# axiom_beta_plugin_module_TE0714_SATA_v0_.net
KiCad netlist of a schematic drawn in EAGLE
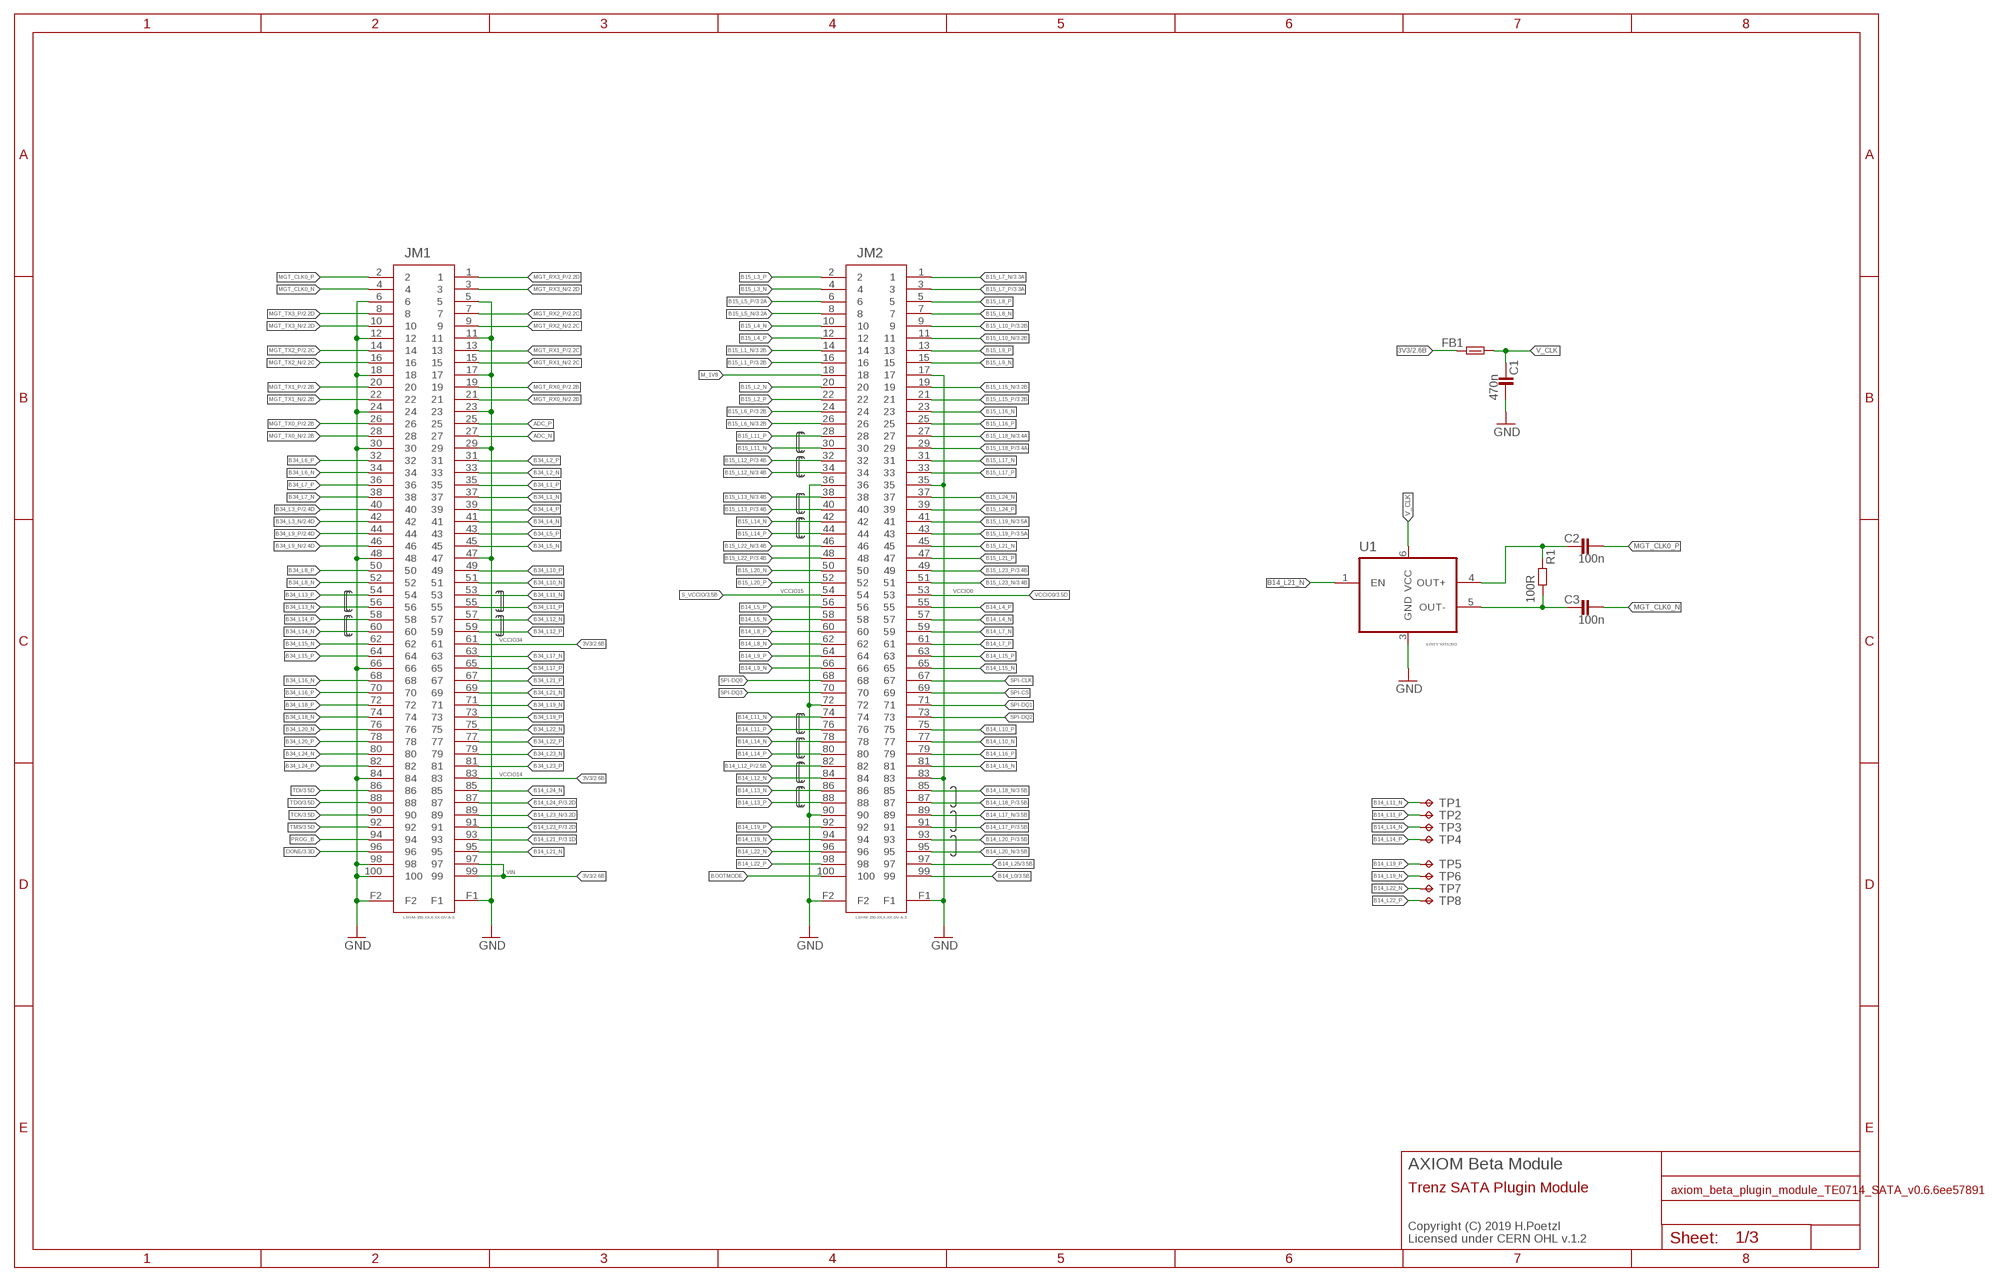
[diagram p0: schematic, sheet 1]
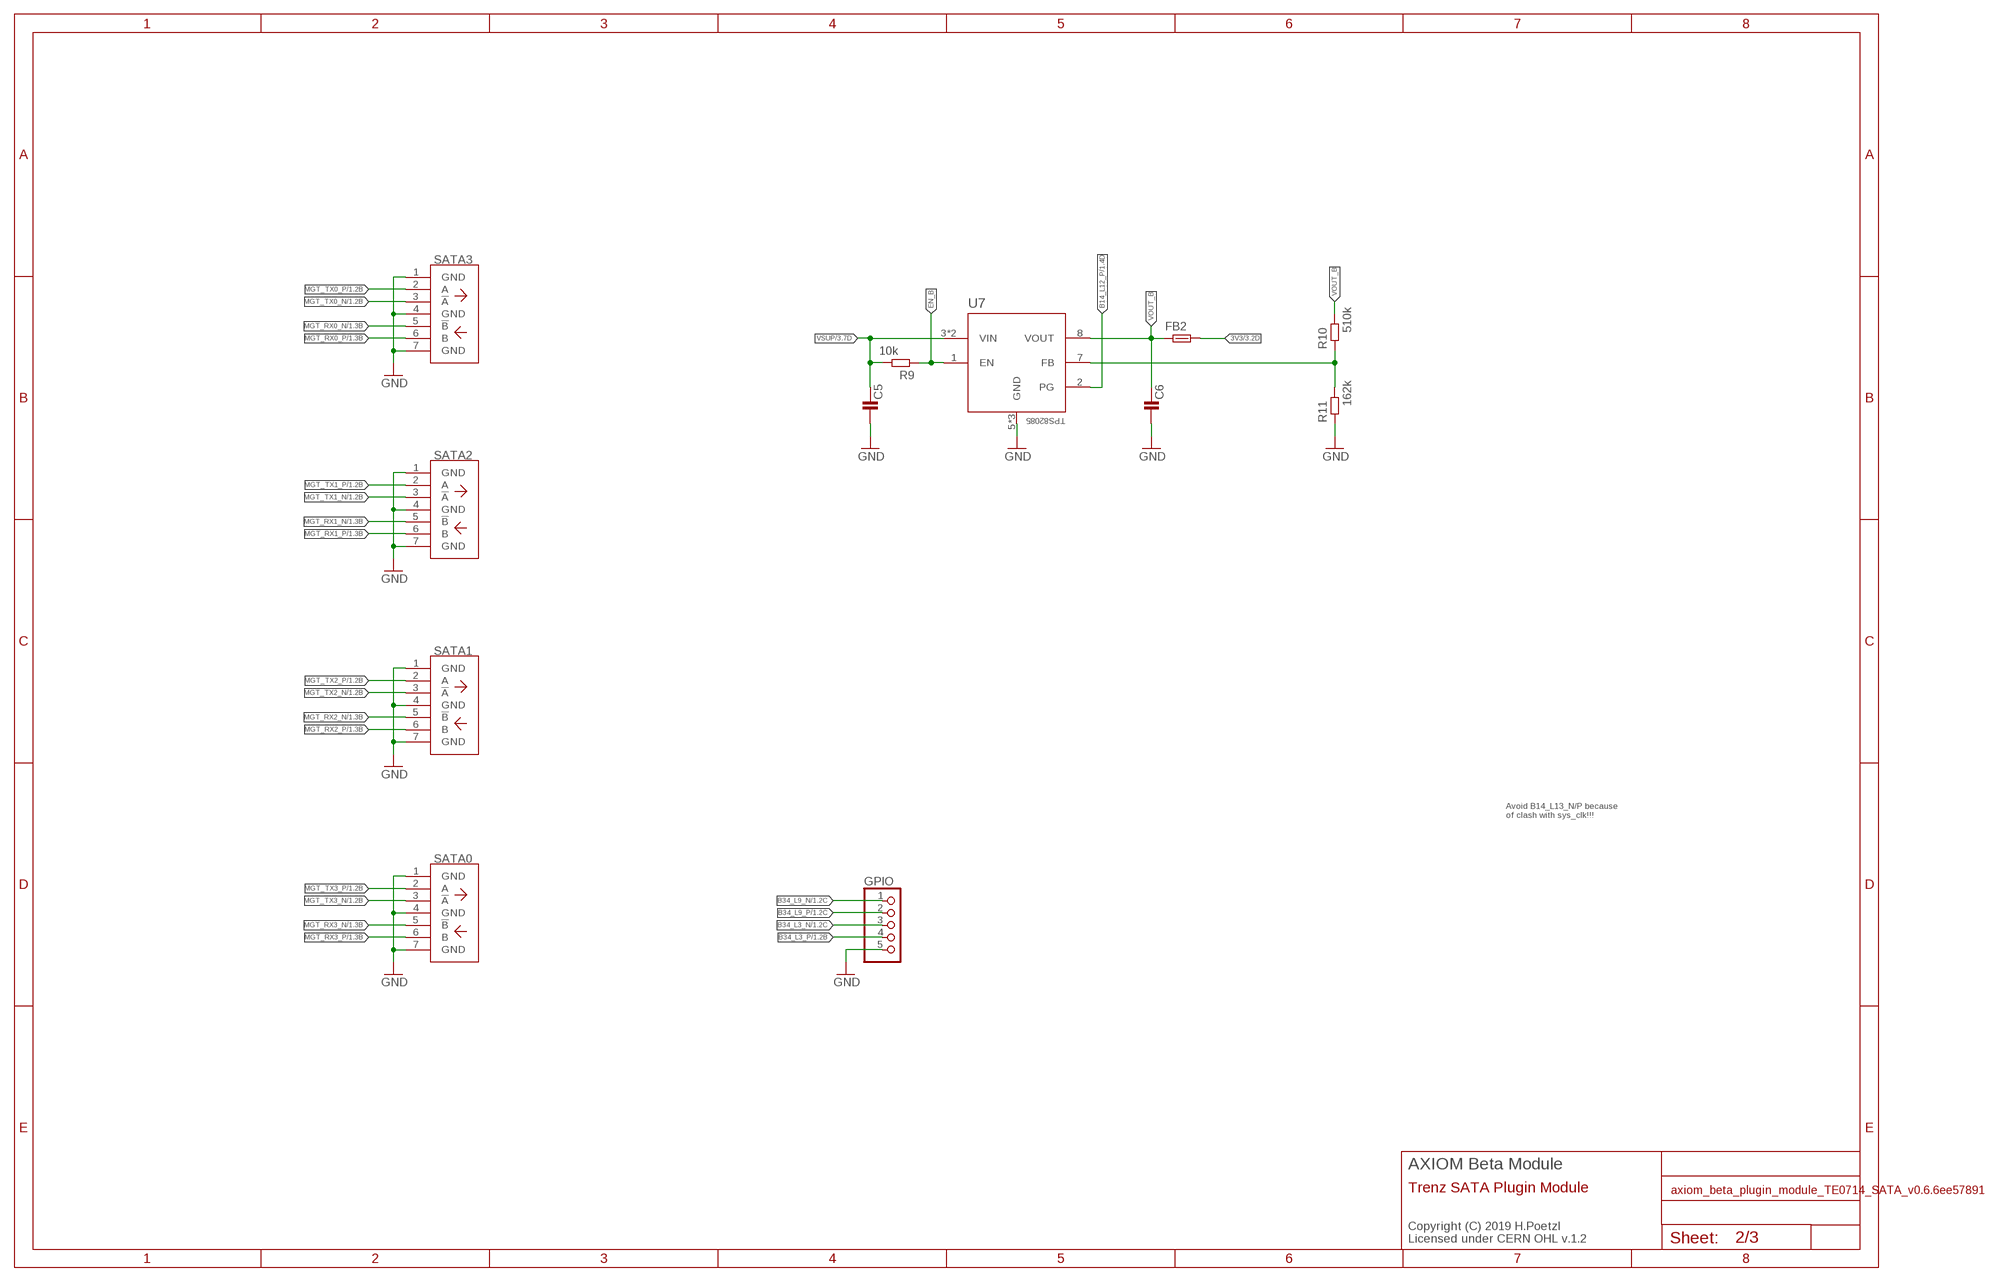
[diagram p1: schematic, sheet 2]
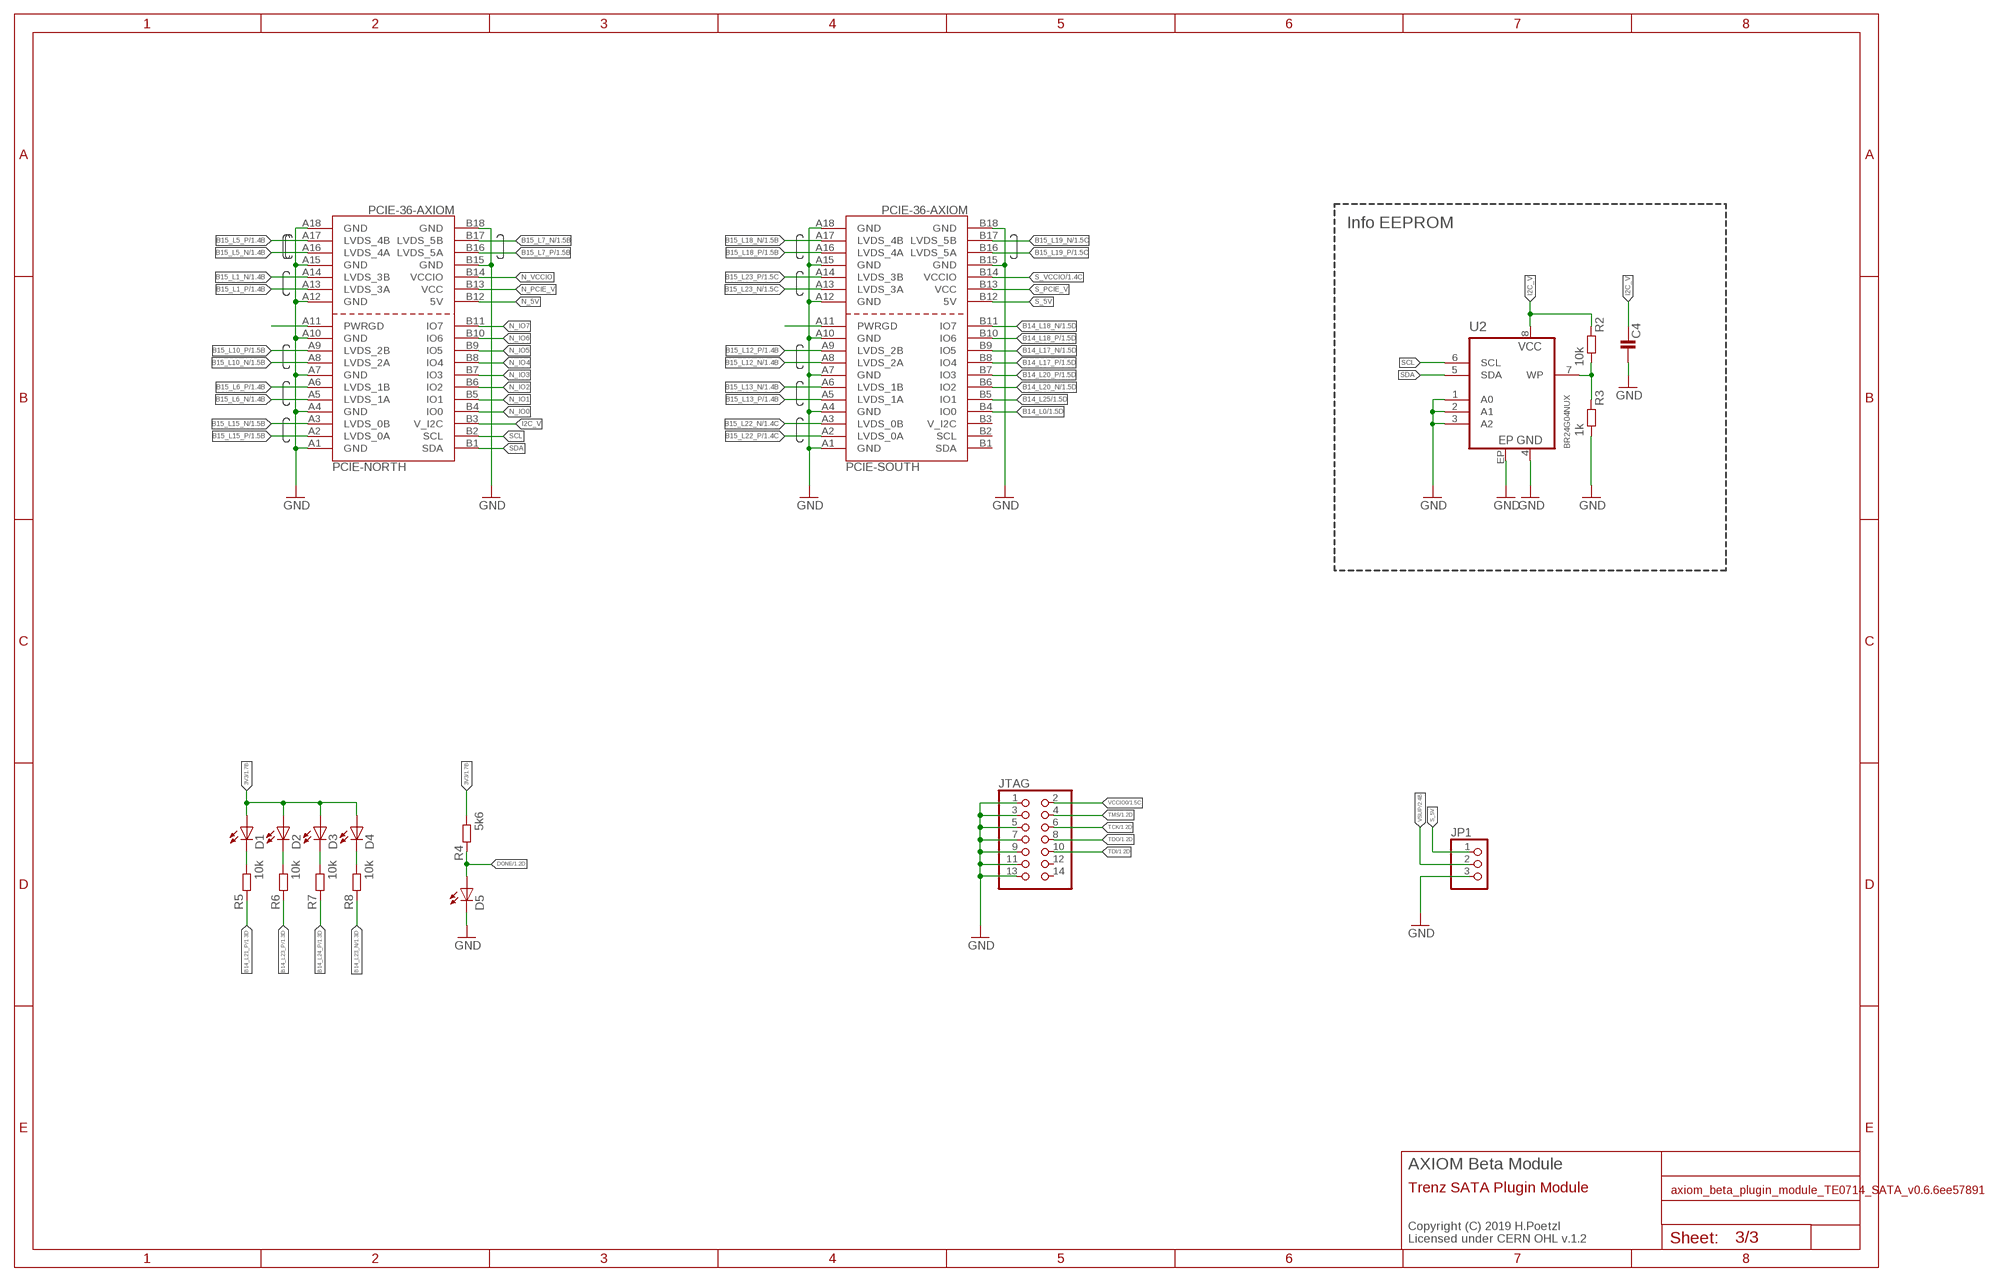
[diagram p2: schematic, sheet 3]

(export (version "E")
  (design (tool "Eeschema 10.0.6"))
  (components
    (comp (ref "C4")
      (value "C0402-B")
      (footprint "eagle-import:0402-B")
      (libsource (lib "eagle-import") (part "C0402-B"))
    )
    (comp (ref "D1")
      (value "LED")
      (footprint "eagle-import:CHIPLED_0603")
      (libsource (lib "eagle-import") (part "LED"))
    )
    (comp (ref "D2")
      (value "LED")
      (footprint "eagle-import:CHIPLED_0603")
      (libsource (lib "eagle-import") (part "LED"))
    )
    (comp (ref "D3")
      (value "LED")
      (footprint "eagle-import:CHIPLED_0603")
      (libsource (lib "eagle-import") (part "LED"))
    )
    (comp (ref "D4")
      (value "LED")
      (footprint "eagle-import:CHIPLED_0603")
      (libsource (lib "eagle-import") (part "LED"))
    )
    (comp (ref "D5")
      (value "LED")
      (footprint "eagle-import:CHIPLED_0603")
      (libsource (lib "eagle-import") (part "LED"))
    )
    (comp (ref "JP1")
      (value "PINHD-1X03_2.54-90°-S")
      (footprint "eagle-import:1X03_90-S")
      (libsource (lib "eagle-import") (part "PINHD-1X03_2.54-90°-S"))
    )
    (comp (ref "JTAG")
      (value "PINHD-2X07_2.00")
      (footprint "eagle-import:2X07M")
      (libsource (lib "eagle-import") (part "PINHD-2X07_2.00"))
    )
    (comp (ref "PCIE-NORTH")
      (value "PCIE-36-AXIOM")
      (footprint "eagle-import:PCIE-36-AXIOM")
      (libsource (lib "eagle-import") (part "PCIE-36-AXIOM"))
    )
    (comp (ref "PCIE-SOUTH")
      (value "PCIE-36-AXIOM")
      (footprint "eagle-import:PCIE-36-AXIOM")
      (libsource (lib "eagle-import") (part "PCIE-36-AXIOM"))
    )
    (comp (ref "R2")
      (value "10k")
      (footprint "eagle-import:0402-B")
      (libsource (lib "eagle-import") (part "R0402-B"))
    )
    (comp (ref "R3")
      (value "1k")
      (footprint "eagle-import:0402-B")
      (libsource (lib "eagle-import") (part "R0402-B"))
    )
    (comp (ref "R4")
      (value "5k6")
      (footprint "eagle-import:0402-C")
      (libsource (lib "eagle-import") (part "R0402-C"))
    )
    (comp (ref "R5")
      (value "10k")
      (footprint "eagle-import:0402-C")
      (libsource (lib "eagle-import") (part "R0402-C"))
    )
    (comp (ref "R6")
      (value "10k")
      (footprint "eagle-import:0402-C")
      (libsource (lib "eagle-import") (part "R0402-C"))
    )
    (comp (ref "R7")
      (value "10k")
      (footprint "eagle-import:0402-C")
      (libsource (lib "eagle-import") (part "R0402-C"))
    )
    (comp (ref "R8")
      (value "10k")
      (footprint "eagle-import:0402-C")
      (libsource (lib "eagle-import") (part "R0402-C"))
    )
    (comp (ref "U2")
      (value "BR24G04NUX")
      (footprint "eagle-import:DFN200X300X100-9N")
      (libsource (lib "eagle-import") (part "BR24G04NUX"))
    )
    (comp (ref "C1")
      (value "470n")
      (footprint "eagle-import:0402-C")
      (libsource (lib "eagle-import") (part "C0402-C"))
    )
    (comp (ref "C2")
      (value "100n")
      (footprint "eagle-import:0201-C")
      (libsource (lib "eagle-import") (part "C0201-C"))
    )
    (comp (ref "C3")
      (value "100n")
      (footprint "eagle-import:0201-C")
      (libsource (lib "eagle-import") (part "C0201-C"))
    )
    (comp (ref "FB1")
      (value "FB0402-C")
      (footprint "eagle-import:0402-C")
      (libsource (lib "eagle-import") (part "FB0402-C"))
    )
    (comp (ref "JM1")
      (value "LSHM-150-XX.X-XX-DV-A-S")
      (footprint "eagle-import:LSHM-150-XX.X-XX-DV-A-S")
      (libsource (lib "eagle-import") (part "LSHM-150-XX.X-XX-DV-A-S"))
    )
    (comp (ref "JM2")
      (value "LSHM-150-XX.X-XX-DV-A-S")
      (footprint "eagle-import:LSHM-150-XX.X-XX-DV-A-S")
      (libsource (lib "eagle-import") (part "LSHM-150-XX.X-XX-DV-A-S"))
    )
    (comp (ref "R1")
      (value "100R")
      (footprint "eagle-import:0201-C")
      (libsource (lib "eagle-import") (part "R0201-C"))
    )
    (comp (ref "TP1")
      (value "TPTP10R")
      (footprint "eagle-import:TP10R")
      (libsource (lib "eagle-import") (part "TPTP10R"))
    )
    (comp (ref "TP2")
      (value "TPTP10R")
      (footprint "eagle-import:TP10R")
      (libsource (lib "eagle-import") (part "TPTP10R"))
    )
    (comp (ref "TP3")
      (value "TPTP10R")
      (footprint "eagle-import:TP10R")
      (libsource (lib "eagle-import") (part "TPTP10R"))
    )
    (comp (ref "TP4")
      (value "TPTP10R")
      (footprint "eagle-import:TP10R")
      (libsource (lib "eagle-import") (part "TPTP10R"))
    )
    (comp (ref "TP5")
      (value "TPTP10R")
      (footprint "eagle-import:TP10R")
      (libsource (lib "eagle-import") (part "TPTP10R"))
    )
    (comp (ref "TP6")
      (value "TPTP10R")
      (footprint "eagle-import:TP10R")
      (libsource (lib "eagle-import") (part "TPTP10R"))
    )
    (comp (ref "TP7")
      (value "TPTP10R")
      (footprint "eagle-import:TP10R")
      (libsource (lib "eagle-import") (part "TPTP10R"))
    )
    (comp (ref "TP8")
      (value "TPTP10R")
      (footprint "eagle-import:TP10R")
      (libsource (lib "eagle-import") (part "TPTP10R"))
    )
    (comp (ref "U1")
      (value "DSC11XX-3.2X2.5")
      (footprint "eagle-import:3.2X2.5")
      (libsource (lib "eagle-import") (part "DSC11XX-3.2X2.5"))
    )
    (comp (ref "C5")
      (value "C0603-C")
      (footprint "eagle-import:0603-C")
      (libsource (lib "eagle-import") (part "C0603-C"))
    )
    (comp (ref "C6")
      (value "C0603-C")
      (footprint "eagle-import:0603-C")
      (libsource (lib "eagle-import") (part "C0603-C"))
    )
    (comp (ref "FB2")
      (value "FB0603-C")
      (footprint "eagle-import:0603-C")
      (libsource (lib "eagle-import") (part "FB0603-C"))
    )
    (comp (ref "GPIO")
      (value "PINHD-1X05_2.00")
      (footprint "eagle-import:1X05M")
      (libsource (lib "eagle-import") (part "PINHD-1X05_2.00"))
    )
    (comp (ref "R9")
      (value "10k")
      (footprint "eagle-import:0201-C")
      (libsource (lib "eagle-import") (part "R0201-C"))
    )
    (comp (ref "R10")
      (value "510k")
      (footprint "eagle-import:0201-C")
      (libsource (lib "eagle-import") (part "R0201-C"))
    )
    (comp (ref "R11")
      (value "162k")
      (footprint "eagle-import:0201-C")
      (libsource (lib "eagle-import") (part "R0201-C"))
    )
    (comp (ref "SATA0")
      (value "SATA7-VERT")
      (footprint "eagle-import:SATA7-VERT")
      (libsource (lib "eagle-import") (part "SATA7-VERT"))
    )
    (comp (ref "SATA1")
      (value "SATA7-VERT")
      (footprint "eagle-import:SATA7-VERT")
      (libsource (lib "eagle-import") (part "SATA7-VERT"))
    )
    (comp (ref "SATA2")
      (value "SATA7-VERT")
      (footprint "eagle-import:SATA7-VERT")
      (libsource (lib "eagle-import") (part "SATA7-VERT"))
    )
    (comp (ref "SATA3")
      (value "SATA7-VERT")
      (footprint "eagle-import:SATA7-VERT")
      (libsource (lib "eagle-import") (part "SATA7-VERT"))
    )
    (comp (ref "U7")
      (value "TPS82085")
      (footprint "eagle-import:MICROSIP")
      (libsource (lib "eagle-import") (part "TPS82085"))
    )
  )
  (nets
    (net (code "1") (name "3V3") (class "Default")
      (node (ref "D1") (pin "A") (pinfunction "A_A") (pintype "passive"))
      (node (ref "D2") (pin "A") (pinfunction "A_A") (pintype "passive"))
      (node (ref "D3") (pin "A") (pinfunction "A_A") (pintype "passive"))
      (node (ref "D4") (pin "A") (pinfunction "A_A") (pintype "passive"))
      (node (ref "FB1") (pin "1") (pinfunction "1_1") (pintype "passive"))
      (node (ref "FB2") (pin "2") (pinfunction "2_2") (pintype "passive"))
      (node (ref "JM1") (pin "61") (pinfunction "61_61") (pintype "bidirectional"))
      (node (ref "JM1") (pin "83") (pinfunction "83_83") (pintype "bidirectional"))
      (node (ref "JM1") (pin "97") (pinfunction "97_97") (pintype "bidirectional"))
      (node (ref "JM1") (pin "99") (pinfunction "99_99") (pintype "bidirectional"))
      (node (ref "R4") (pin "2") (pinfunction "2_2") (pintype "passive"))
    )
    (net (code "2") (name "ADC_N") (class "Default")
      (node (ref "JM1") (pin "27") (pinfunction "27_27") (pintype "bidirectional"))
    )
    (net (code "3") (name "ADC_P") (class "Default")
      (node (ref "JM1") (pin "25") (pinfunction "25_25") (pintype "bidirectional"))
    )
    (net (code "4") (name "B14_L0") (class "Default")
      (node (ref "JM2") (pin "99") (pinfunction "99_99") (pintype "bidirectional"))
      (node (ref "PCIE-SOUTH") (pin "B4") (pinfunction "IO0_B4") (pintype "passive"))
    )
    (net (code "5") (name "B14_L4_N") (class "Default")
      (node (ref "JM2") (pin "57") (pinfunction "57_57") (pintype "bidirectional"))
    )
    (net (code "6") (name "B14_L4_P") (class "Default")
      (node (ref "JM2") (pin "55") (pinfunction "55_55") (pintype "bidirectional"))
    )
    (net (code "7") (name "B14_L5_N") (class "Default")
      (node (ref "JM2") (pin "58") (pinfunction "58_58") (pintype "bidirectional"))
    )
    (net (code "8") (name "B14_L5_P") (class "Default")
      (node (ref "JM2") (pin "56") (pinfunction "56_56") (pintype "bidirectional"))
    )
    (net (code "9") (name "B14_L7_N") (class "Default")
      (node (ref "JM2") (pin "59") (pinfunction "59_59") (pintype "bidirectional"))
    )
    (net (code "10") (name "B14_L7_P") (class "Default")
      (node (ref "JM2") (pin "61") (pinfunction "61_61") (pintype "bidirectional"))
    )
    (net (code "11") (name "B14_L8_N") (class "Default")
      (node (ref "JM2") (pin "62") (pinfunction "62_62") (pintype "bidirectional"))
    )
    (net (code "12") (name "B14_L8_P") (class "Default")
      (node (ref "JM2") (pin "60") (pinfunction "60_60") (pintype "bidirectional"))
    )
    (net (code "13") (name "B14_L9_N") (class "Default")
      (node (ref "JM2") (pin "66") (pinfunction "66_66") (pintype "bidirectional"))
    )
    (net (code "14") (name "B14_L9_P") (class "Default")
      (node (ref "JM2") (pin "64") (pinfunction "64_64") (pintype "bidirectional"))
    )
    (net (code "15") (name "B14_L10_N") (class "Default")
      (node (ref "JM2") (pin "77") (pinfunction "77_77") (pintype "bidirectional"))
    )
    (net (code "16") (name "B14_L10_P") (class "Default")
      (node (ref "JM2") (pin "75") (pinfunction "75_75") (pintype "bidirectional"))
    )
    (net (code "17") (name "B14_L11_N") (class "Default")
      (node (ref "JM2") (pin "74") (pinfunction "74_74") (pintype "bidirectional"))
      (node (ref "TP1") (pin "TP") (pinfunction "TP_TP") (pintype "input"))
    )
    (net (code "18") (name "B14_L11_P") (class "Default")
      (node (ref "JM2") (pin "76") (pinfunction "76_76") (pintype "bidirectional"))
      (node (ref "TP2") (pin "TP") (pinfunction "TP_TP") (pintype "input"))
    )
    (net (code "19") (name "B14_L12_N") (class "Default")
      (node (ref "JM2") (pin "84") (pinfunction "84_84") (pintype "bidirectional"))
    )
    (net (code "20") (name "B14_L12_P") (class "Default")
      (node (ref "JM2") (pin "82") (pinfunction "82_82") (pintype "bidirectional"))
      (node (ref "U7") (pin "2") (pinfunction "PG_2") (pintype "power_in"))
    )
    (net (code "21") (name "B14_L13_N") (class "Default")
      (node (ref "JM2") (pin "86") (pinfunction "86_86") (pintype "bidirectional"))
    )
    (net (code "22") (name "B14_L13_P") (class "Default")
      (node (ref "JM2") (pin "88") (pinfunction "88_88") (pintype "bidirectional"))
    )
    (net (code "23") (name "B14_L14_N") (class "Default")
      (node (ref "JM2") (pin "78") (pinfunction "78_78") (pintype "bidirectional"))
      (node (ref "TP3") (pin "TP") (pinfunction "TP_TP") (pintype "input"))
    )
    (net (code "24") (name "B14_L14_P") (class "Default")
      (node (ref "JM2") (pin "80") (pinfunction "80_80") (pintype "bidirectional"))
      (node (ref "TP4") (pin "TP") (pinfunction "TP_TP") (pintype "input"))
    )
    (net (code "25") (name "B14_L15_N") (class "Default")
      (node (ref "JM2") (pin "65") (pinfunction "65_65") (pintype "bidirectional"))
    )
    (net (code "26") (name "B14_L15_P") (class "Default")
      (node (ref "JM2") (pin "63") (pinfunction "63_63") (pintype "bidirectional"))
    )
    (net (code "27") (name "B14_L16_N") (class "Default")
      (node (ref "JM2") (pin "81") (pinfunction "81_81") (pintype "bidirectional"))
    )
    (net (code "28") (name "B14_L16_P") (class "Default")
      (node (ref "JM2") (pin "79") (pinfunction "79_79") (pintype "bidirectional"))
    )
    (net (code "29") (name "B14_L17_N") (class "Default")
      (node (ref "JM2") (pin "89") (pinfunction "89_89") (pintype "bidirectional"))
      (node (ref "PCIE-SOUTH") (pin "B9") (pinfunction "IO5_B9") (pintype "passive"))
    )
    (net (code "30") (name "B14_L17_P") (class "Default")
      (node (ref "JM2") (pin "91") (pinfunction "91_91") (pintype "bidirectional"))
      (node (ref "PCIE-SOUTH") (pin "B8") (pinfunction "IO4_B8") (pintype "passive"))
    )
    (net (code "31") (name "B14_L18_N") (class "Default")
      (node (ref "JM2") (pin "85") (pinfunction "85_85") (pintype "bidirectional"))
      (node (ref "PCIE-SOUTH") (pin "B11") (pinfunction "IO7_B11") (pintype "passive"))
    )
    (net (code "32") (name "B14_L18_P") (class "Default")
      (node (ref "JM2") (pin "87") (pinfunction "87_87") (pintype "bidirectional"))
      (node (ref "PCIE-SOUTH") (pin "B10") (pinfunction "IO6_B10") (pintype "passive"))
    )
    (net (code "33") (name "B14_L19_N") (class "Default")
      (node (ref "JM2") (pin "94") (pinfunction "94_94") (pintype "bidirectional"))
      (node (ref "TP6") (pin "TP") (pinfunction "TP_TP") (pintype "input"))
    )
    (net (code "34") (name "B14_L19_P") (class "Default")
      (node (ref "JM2") (pin "92") (pinfunction "92_92") (pintype "bidirectional"))
      (node (ref "TP5") (pin "TP") (pinfunction "TP_TP") (pintype "input"))
    )
    (net (code "35") (name "B14_L20_N") (class "Default")
      (node (ref "JM2") (pin "95") (pinfunction "95_95") (pintype "bidirectional"))
      (node (ref "PCIE-SOUTH") (pin "B6") (pinfunction "IO2_B6") (pintype "passive"))
    )
    (net (code "36") (name "B14_L20_P") (class "Default")
      (node (ref "JM2") (pin "93") (pinfunction "93_93") (pintype "bidirectional"))
      (node (ref "PCIE-SOUTH") (pin "B7") (pinfunction "IO3_B7") (pintype "passive"))
    )
    (net (code "37") (name "B14_L21_N") (class "Default")
      (node (ref "JM1") (pin "95") (pinfunction "95_95") (pintype "bidirectional"))
      (node (ref "U1") (pin "1") (pinfunction "EN_1") (pintype "input"))
    )
    (net (code "38") (name "B14_L21_P") (class "Default")
      (node (ref "JM1") (pin "93") (pinfunction "93_93") (pintype "bidirectional"))
      (node (ref "R5") (pin "1") (pinfunction "1_1") (pintype "passive"))
    )
    (net (code "39") (name "B14_L22_N") (class "Default")
      (node (ref "JM2") (pin "96") (pinfunction "96_96") (pintype "bidirectional"))
      (node (ref "TP7") (pin "TP") (pinfunction "TP_TP") (pintype "input"))
    )
    (net (code "40") (name "B14_L22_P") (class "Default")
      (node (ref "JM2") (pin "98") (pinfunction "98_98") (pintype "bidirectional"))
      (node (ref "TP8") (pin "TP") (pinfunction "TP_TP") (pintype "input"))
    )
    (net (code "41") (name "B14_L23_N") (class "Default")
      (node (ref "JM1") (pin "89") (pinfunction "89_89") (pintype "bidirectional"))
      (node (ref "R8") (pin "1") (pinfunction "1_1") (pintype "passive"))
    )
    (net (code "42") (name "B14_L23_P") (class "Default")
      (node (ref "JM1") (pin "91") (pinfunction "91_91") (pintype "bidirectional"))
      (node (ref "R6") (pin "1") (pinfunction "1_1") (pintype "passive"))
    )
    (net (code "43") (name "B14_L24_N") (class "Default")
      (node (ref "JM1") (pin "85") (pinfunction "85_85") (pintype "bidirectional"))
    )
    (net (code "44") (name "B14_L24_P") (class "Default")
      (node (ref "JM1") (pin "87") (pinfunction "87_87") (pintype "bidirectional"))
      (node (ref "R7") (pin "1") (pinfunction "1_1") (pintype "passive"))
    )
    (net (code "45") (name "B14_L25") (class "Default")
      (node (ref "JM2") (pin "97") (pinfunction "97_97") (pintype "bidirectional"))
      (node (ref "PCIE-SOUTH") (pin "B5") (pinfunction "IO1_B5") (pintype "passive"))
    )
    (net (code "46") (name "B15_L1_N") (class "Default")
      (node (ref "JM2") (pin "14") (pinfunction "14_14") (pintype "bidirectional"))
      (node (ref "PCIE-NORTH") (pin "A14") (pinfunction "LVDS_3B_A14") (pintype "passive"))
    )
    (net (code "47") (name "B15_L1_P") (class "Default")
      (node (ref "JM2") (pin "16") (pinfunction "16_16") (pintype "bidirectional"))
      (node (ref "PCIE-NORTH") (pin "A13") (pinfunction "LVDS_3A_A13") (pintype "passive"))
    )
    (net (code "48") (name "B15_L2_N") (class "Default")
      (node (ref "JM2") (pin "20") (pinfunction "20_20") (pintype "bidirectional"))
    )
    (net (code "49") (name "B15_L2_P") (class "Default")
      (node (ref "JM2") (pin "22") (pinfunction "22_22") (pintype "bidirectional"))
    )
    (net (code "50") (name "B15_L3_N") (class "Default")
      (node (ref "JM2") (pin "4") (pinfunction "4_4") (pintype "bidirectional"))
    )
    (net (code "51") (name "B15_L3_P") (class "Default")
      (node (ref "JM2") (pin "2") (pinfunction "2_2") (pintype "bidirectional"))
    )
    (net (code "52") (name "B15_L4_N") (class "Default")
      (node (ref "JM2") (pin "10") (pinfunction "10_10") (pintype "bidirectional"))
    )
    (net (code "53") (name "B15_L4_P") (class "Default")
      (node (ref "JM2") (pin "12") (pinfunction "12_12") (pintype "bidirectional"))
    )
    (net (code "54") (name "B15_L5_N") (class "Default")
      (node (ref "JM2") (pin "8") (pinfunction "8_8") (pintype "bidirectional"))
      (node (ref "PCIE-NORTH") (pin "A16") (pinfunction "LVDS_4A_A16") (pintype "passive"))
    )
    (net (code "55") (name "B15_L5_P") (class "Default")
      (node (ref "JM2") (pin "6") (pinfunction "6_6") (pintype "bidirectional"))
      (node (ref "PCIE-NORTH") (pin "A17") (pinfunction "LVDS_4B_A17") (pintype "passive"))
    )
    (net (code "56") (name "B15_L6_N") (class "Default")
      (node (ref "JM2") (pin "26") (pinfunction "26_26") (pintype "bidirectional"))
      (node (ref "PCIE-NORTH") (pin "A5") (pinfunction "LVDS_1A_A5") (pintype "passive"))
    )
    (net (code "57") (name "B15_L6_P") (class "Default")
      (node (ref "JM2") (pin "24") (pinfunction "24_24") (pintype "bidirectional"))
      (node (ref "PCIE-NORTH") (pin "A6") (pinfunction "LVDS_1B_A6") (pintype "passive"))
    )
    (net (code "58") (name "B15_L7_N") (class "Default")
      (node (ref "JM2") (pin "1") (pinfunction "1_1") (pintype "bidirectional"))
      (node (ref "PCIE-NORTH") (pin "B17") (pinfunction "LVDS_5B_B17") (pintype "passive"))
    )
    (net (code "59") (name "B15_L7_P") (class "Default")
      (node (ref "JM2") (pin "3") (pinfunction "3_3") (pintype "bidirectional"))
      (node (ref "PCIE-NORTH") (pin "B16") (pinfunction "LVDS_5A_B16") (pintype "passive"))
    )
    (net (code "60") (name "B15_L8_N") (class "Default")
      (node (ref "JM2") (pin "7") (pinfunction "7_7") (pintype "bidirectional"))
    )
    (net (code "61") (name "B15_L8_P") (class "Default")
      (node (ref "JM2") (pin "5") (pinfunction "5_5") (pintype "bidirectional"))
    )
    (net (code "62") (name "B15_L9_N") (class "Default")
      (node (ref "JM2") (pin "15") (pinfunction "15_15") (pintype "bidirectional"))
    )
    (net (code "63") (name "B15_L9_P") (class "Default")
      (node (ref "JM2") (pin "13") (pinfunction "13_13") (pintype "bidirectional"))
    )
    (net (code "64") (name "B15_L10_N") (class "Default")
      (node (ref "JM2") (pin "11") (pinfunction "11_11") (pintype "bidirectional"))
      (node (ref "PCIE-NORTH") (pin "A8") (pinfunction "LVDS_2A_A8") (pintype "passive"))
    )
    (net (code "65") (name "B15_L10_P") (class "Default")
      (node (ref "JM2") (pin "9") (pinfunction "9_9") (pintype "bidirectional"))
      (node (ref "PCIE-NORTH") (pin "A9") (pinfunction "LVDS_2B_A9") (pintype "passive"))
    )
    (net (code "66") (name "B15_L11_N") (class "Default")
      (node (ref "JM2") (pin "30") (pinfunction "30_30") (pintype "bidirectional"))
    )
    (net (code "67") (name "B15_L11_P") (class "Default")
      (node (ref "JM2") (pin "28") (pinfunction "28_28") (pintype "bidirectional"))
    )
    (net (code "68") (name "B15_L12_N") (class "Default")
      (node (ref "JM2") (pin "34") (pinfunction "34_34") (pintype "bidirectional"))
      (node (ref "PCIE-SOUTH") (pin "A8") (pinfunction "LVDS_2A_A8") (pintype "passive"))
    )
    (net (code "69") (name "B15_L12_P") (class "Default")
      (node (ref "JM2") (pin "32") (pinfunction "32_32") (pintype "bidirectional"))
      (node (ref "PCIE-SOUTH") (pin "A9") (pinfunction "LVDS_2B_A9") (pintype "passive"))
    )
    (net (code "70") (name "B15_L13_N") (class "Default")
      (node (ref "JM2") (pin "38") (pinfunction "38_38") (pintype "bidirectional"))
      (node (ref "PCIE-SOUTH") (pin "A6") (pinfunction "LVDS_1B_A6") (pintype "passive"))
    )
    (net (code "71") (name "B15_L13_P") (class "Default")
      (node (ref "JM2") (pin "40") (pinfunction "40_40") (pintype "bidirectional"))
      (node (ref "PCIE-SOUTH") (pin "A5") (pinfunction "LVDS_1A_A5") (pintype "passive"))
    )
    (net (code "72") (name "B15_L14_N") (class "Default")
      (node (ref "JM2") (pin "42") (pinfunction "42_42") (pintype "bidirectional"))
    )
    (net (code "73") (name "B15_L14_P") (class "Default")
      (node (ref "JM2") (pin "44") (pinfunction "44_44") (pintype "bidirectional"))
    )
    (net (code "74") (name "B15_L15_N") (class "Default")
      (node (ref "JM2") (pin "19") (pinfunction "19_19") (pintype "bidirectional"))
      (node (ref "PCIE-NORTH") (pin "A3") (pinfunction "LVDS_0B_A3") (pintype "passive"))
    )
    (net (code "75") (name "B15_L15_P") (class "Default")
      (node (ref "JM2") (pin "21") (pinfunction "21_21") (pintype "bidirectional"))
      (node (ref "PCIE-NORTH") (pin "A2") (pinfunction "LVDS_0A_A2") (pintype "passive"))
    )
    (net (code "76") (name "B15_L16_N") (class "Default")
      (node (ref "JM2") (pin "23") (pinfunction "23_23") (pintype "bidirectional"))
    )
    (net (code "77") (name "B15_L16_P") (class "Default")
      (node (ref "JM2") (pin "25") (pinfunction "25_25") (pintype "bidirectional"))
    )
    (net (code "78") (name "B15_L17_N") (class "Default")
      (node (ref "JM2") (pin "31") (pinfunction "31_31") (pintype "bidirectional"))
    )
    (net (code "79") (name "B15_L17_P") (class "Default")
      (node (ref "JM2") (pin "33") (pinfunction "33_33") (pintype "bidirectional"))
    )
    (net (code "80") (name "B15_L18_N") (class "Default")
      (node (ref "JM2") (pin "27") (pinfunction "27_27") (pintype "bidirectional"))
      (node (ref "PCIE-SOUTH") (pin "A17") (pinfunction "LVDS_4B_A17") (pintype "passive"))
    )
    (net (code "81") (name "B15_L18_P") (class "Default")
      (node (ref "JM2") (pin "29") (pinfunction "29_29") (pintype "bidirectional"))
      (node (ref "PCIE-SOUTH") (pin "A16") (pinfunction "LVDS_4A_A16") (pintype "passive"))
    )
    (net (code "82") (name "B15_L19_N") (class "Default")
      (node (ref "JM2") (pin "41") (pinfunction "41_41") (pintype "bidirectional"))
      (node (ref "PCIE-SOUTH") (pin "B17") (pinfunction "LVDS_5B_B17") (pintype "passive"))
    )
    (net (code "83") (name "B15_L19_P") (class "Default")
      (node (ref "JM2") (pin "43") (pinfunction "43_43") (pintype "bidirectional"))
      (node (ref "PCIE-SOUTH") (pin "B16") (pinfunction "LVDS_5A_B16") (pintype "passive"))
    )
    (net (code "84") (name "B15_L20_N") (class "Default")
      (node (ref "JM2") (pin "50") (pinfunction "50_50") (pintype "bidirectional"))
    )
    (net (code "85") (name "B15_L20_P") (class "Default")
      (node (ref "JM2") (pin "52") (pinfunction "52_52") (pintype "bidirectional"))
    )
    (net (code "86") (name "B15_L21_N") (class "Default")
      (node (ref "JM2") (pin "45") (pinfunction "45_45") (pintype "bidirectional"))
    )
    (net (code "87") (name "B15_L21_P") (class "Default")
      (node (ref "JM2") (pin "47") (pinfunction "47_47") (pintype "bidirectional"))
    )
    (net (code "88") (name "B15_L22_N") (class "Default")
      (node (ref "JM2") (pin "46") (pinfunction "46_46") (pintype "bidirectional"))
      (node (ref "PCIE-SOUTH") (pin "A3") (pinfunction "LVDS_0B_A3") (pintype "passive"))
    )
    (net (code "89") (name "B15_L22_P") (class "Default")
      (node (ref "JM2") (pin "48") (pinfunction "48_48") (pintype "bidirectional"))
      (node (ref "PCIE-SOUTH") (pin "A2") (pinfunction "LVDS_0A_A2") (pintype "passive"))
    )
    (net (code "90") (name "B15_L23_N") (class "Default")
      (node (ref "JM2") (pin "51") (pinfunction "51_51") (pintype "bidirectional"))
      (node (ref "PCIE-SOUTH") (pin "A13") (pinfunction "LVDS_3A_A13") (pintype "passive"))
    )
    (net (code "91") (name "B15_L23_P") (class "Default")
      (node (ref "JM2") (pin "49") (pinfunction "49_49") (pintype "bidirectional"))
      (node (ref "PCIE-SOUTH") (pin "A14") (pinfunction "LVDS_3B_A14") (pintype "passive"))
    )
    (net (code "92") (name "B15_L24_N") (class "Default")
      (node (ref "JM2") (pin "37") (pinfunction "37_37") (pintype "bidirectional"))
    )
    (net (code "93") (name "B15_L24_P") (class "Default")
      (node (ref "JM2") (pin "39") (pinfunction "39_39") (pintype "bidirectional"))
    )
    (net (code "94") (name "B34_L1_N") (class "Default")
      (node (ref "JM1") (pin "37") (pinfunction "37_37") (pintype "bidirectional"))
    )
    (net (code "95") (name "B34_L1_P") (class "Default")
      (node (ref "JM1") (pin "35") (pinfunction "35_35") (pintype "bidirectional"))
    )
    (net (code "96") (name "B34_L2_N") (class "Default")
      (node (ref "JM1") (pin "33") (pinfunction "33_33") (pintype "bidirectional"))
    )
    (net (code "97") (name "B34_L2_P") (class "Default")
      (node (ref "JM1") (pin "31") (pinfunction "31_31") (pintype "bidirectional"))
    )
    (net (code "98") (name "B34_L3_N") (class "Default")
      (node (ref "GPIO") (pin "3") (pinfunction "3_3") (pintype "passive"))
      (node (ref "JM1") (pin "42") (pinfunction "42_42") (pintype "bidirectional"))
    )
    (net (code "99") (name "B34_L3_P") (class "Default")
      (node (ref "GPIO") (pin "4") (pinfunction "4_4") (pintype "passive"))
      (node (ref "JM1") (pin "40") (pinfunction "40_40") (pintype "bidirectional"))
    )
    (net (code "100") (name "B34_L4_N") (class "Default")
      (node (ref "JM1") (pin "41") (pinfunction "41_41") (pintype "bidirectional"))
    )
    (net (code "101") (name "B34_L4_P") (class "Default")
      (node (ref "JM1") (pin "39") (pinfunction "39_39") (pintype "bidirectional"))
    )
    (net (code "102") (name "B34_L5_N") (class "Default")
      (node (ref "JM1") (pin "45") (pinfunction "45_45") (pintype "bidirectional"))
    )
    (net (code "103") (name "B34_L5_P") (class "Default")
      (node (ref "JM1") (pin "43") (pinfunction "43_43") (pintype "bidirectional"))
    )
    (net (code "104") (name "B34_L6_N") (class "Default")
      (node (ref "JM1") (pin "34") (pinfunction "34_34") (pintype "bidirectional"))
    )
    (net (code "105") (name "B34_L6_P") (class "Default")
      (node (ref "JM1") (pin "32") (pinfunction "32_32") (pintype "bidirectional"))
    )
    (net (code "106") (name "B34_L7_N") (class "Default")
      (node (ref "JM1") (pin "38") (pinfunction "38_38") (pintype "bidirectional"))
    )
    (net (code "107") (name "B34_L7_P") (class "Default")
      (node (ref "JM1") (pin "36") (pinfunction "36_36") (pintype "bidirectional"))
    )
    (net (code "108") (name "B34_L8_N") (class "Default")
      (node (ref "JM1") (pin "52") (pinfunction "52_52") (pintype "bidirectional"))
    )
    (net (code "109") (name "B34_L8_P") (class "Default")
      (node (ref "JM1") (pin "50") (pinfunction "50_50") (pintype "bidirectional"))
    )
    (net (code "110") (name "B34_L9_N") (class "Default")
      (node (ref "GPIO") (pin "1") (pinfunction "1_1") (pintype "passive"))
      (node (ref "JM1") (pin "46") (pinfunction "46_46") (pintype "bidirectional"))
    )
    (net (code "111") (name "B34_L9_P") (class "Default")
      (node (ref "GPIO") (pin "2") (pinfunction "2_2") (pintype "passive"))
      (node (ref "JM1") (pin "44") (pinfunction "44_44") (pintype "bidirectional"))
    )
    (net (code "112") (name "B34_L10_N") (class "Default")
      (node (ref "JM1") (pin "51") (pinfunction "51_51") (pintype "bidirectional"))
    )
    (net (code "113") (name "B34_L10_P") (class "Default")
      (node (ref "JM1") (pin "49") (pinfunction "49_49") (pintype "bidirectional"))
    )
    (net (code "114") (name "B34_L11_N") (class "Default")
      (node (ref "JM1") (pin "53") (pinfunction "53_53") (pintype "bidirectional"))
    )
    (net (code "115") (name "B34_L11_P") (class "Default")
      (node (ref "JM1") (pin "55") (pinfunction "55_55") (pintype "bidirectional"))
    )
    (net (code "116") (name "B34_L12_N") (class "Default")
      (node (ref "JM1") (pin "57") (pinfunction "57_57") (pintype "bidirectional"))
    )
    (net (code "117") (name "B34_L12_P") (class "Default")
      (node (ref "JM1") (pin "59") (pinfunction "59_59") (pintype "bidirectional"))
    )
    (net (code "118") (name "B34_L13_N") (class "Default")
      (node (ref "JM1") (pin "56") (pinfunction "56_56") (pintype "bidirectional"))
    )
    (net (code "119") (name "B34_L13_P") (class "Default")
      (node (ref "JM1") (pin "54") (pinfunction "54_54") (pintype "bidirectional"))
    )
    (net (code "120") (name "B34_L14_N") (class "Default")
      (node (ref "JM1") (pin "60") (pinfunction "60_60") (pintype "bidirectional"))
    )
    (net (code "121") (name "B34_L14_P") (class "Default")
      (node (ref "JM1") (pin "58") (pinfunction "58_58") (pintype "bidirectional"))
    )
    (net (code "122") (name "B34_L15_N") (class "Default")
      (node (ref "JM1") (pin "62") (pinfunction "62_62") (pintype "bidirectional"))
    )
    (net (code "123") (name "B34_L15_P") (class "Default")
      (node (ref "JM1") (pin "64") (pinfunction "64_64") (pintype "bidirectional"))
    )
    (net (code "124") (name "B34_L16_N") (class "Default")
      (node (ref "JM1") (pin "68") (pinfunction "68_68") (pintype "bidirectional"))
    )
    (net (code "125") (name "B34_L16_P") (class "Default")
      (node (ref "JM1") (pin "70") (pinfunction "70_70") (pintype "bidirectional"))
    )
    (net (code "126") (name "B34_L17_N") (class "Default")
      (node (ref "JM1") (pin "63") (pinfunction "63_63") (pintype "bidirectional"))
    )
    (net (code "127") (name "B34_L17_P") (class "Default")
      (node (ref "JM1") (pin "65") (pinfunction "65_65") (pintype "bidirectional"))
    )
    (net (code "128") (name "B34_L18_N") (class "Default")
      (node (ref "JM1") (pin "74") (pinfunction "74_74") (pintype "bidirectional"))
    )
    (net (code "129") (name "B34_L18_P") (class "Default")
      (node (ref "JM1") (pin "72") (pinfunction "72_72") (pintype "bidirectional"))
    )
    (net (code "130") (name "B34_L19_N") (class "Default")
      (node (ref "JM1") (pin "71") (pinfunction "71_71") (pintype "bidirectional"))
    )
    (net (code "131") (name "B34_L19_P") (class "Default")
      (node (ref "JM1") (pin "73") (pinfunction "73_73") (pintype "bidirectional"))
    )
    (net (code "132") (name "B34_L20_N") (class "Default")
      (node (ref "JM1") (pin "76") (pinfunction "76_76") (pintype "bidirectional"))
    )
    (net (code "133") (name "B34_L20_P") (class "Default")
      (node (ref "JM1") (pin "78") (pinfunction "78_78") (pintype "bidirectional"))
    )
    (net (code "134") (name "B34_L21_N") (class "Default")
      (node (ref "JM1") (pin "69") (pinfunction "69_69") (pintype "bidirectional"))
    )
    (net (code "135") (name "B34_L21_P") (class "Default")
      (node (ref "JM1") (pin "67") (pinfunction "67_67") (pintype "bidirectional"))
    )
    (net (code "136") (name "B34_L22_N") (class "Default")
      (node (ref "JM1") (pin "75") (pinfunction "75_75") (pintype "bidirectional"))
    )
    (net (code "137") (name "B34_L22_P") (class "Default")
      (node (ref "JM1") (pin "77") (pinfunction "77_77") (pintype "bidirectional"))
    )
    (net (code "138") (name "B34_L23_N") (class "Default")
      (node (ref "JM1") (pin "79") (pinfunction "79_79") (pintype "bidirectional"))
    )
    (net (code "139") (name "B34_L23_P") (class "Default")
      (node (ref "JM1") (pin "81") (pinfunction "81_81") (pintype "bidirectional"))
    )
    (net (code "140") (name "B34_L24_N") (class "Default")
      (node (ref "JM1") (pin "80") (pinfunction "80_80") (pintype "bidirectional"))
    )
    (net (code "141") (name "B34_L24_P") (class "Default")
      (node (ref "JM1") (pin "82") (pinfunction "82_82") (pintype "bidirectional"))
    )
    (net (code "142") (name "BOOTMODE") (class "Default")
      (node (ref "JM2") (pin "100") (pinfunction "100_100") (pintype "bidirectional"))
    )
    (net (code "143") (name "DONE") (class "Default")
      (node (ref "D5") (pin "A") (pinfunction "A_A") (pintype "passive"))
      (node (ref "JM1") (pin "96") (pinfunction "96_96") (pintype "bidirectional"))
      (node (ref "R4") (pin "1") (pinfunction "1_1") (pintype "passive"))
    )
    (net (code "144") (name "EN_B") (class "Default")
      (node (ref "R9") (pin "1") (pinfunction "1_1") (pintype "passive"))
      (node (ref "U7") (pin "1") (pinfunction "EN_1") (pintype "input"))
    )
    (net (code "145") (name "GND") (class "Default")
      (node (ref "C1") (pin "2") (pinfunction "2_2") (pintype "passive"))
      (node (ref "C4") (pin "2") (pinfunction "2_2") (pintype "passive"))
      (node (ref "C5") (pin "2") (pinfunction "2_2") (pintype "passive"))
      (node (ref "C6") (pin "2") (pinfunction "2_2") (pintype "passive"))
      (node (ref "D5") (pin "C") (pinfunction "C_C") (pintype "passive"))
      (node (ref "GPIO") (pin "5") (pinfunction "5_5") (pintype "passive"))
      (node (ref "JM1") (pin "100") (pinfunction "100_100") (pintype "bidirectional"))
      (node (ref "JM1") (pin "11") (pinfunction "11_11") (pintype "bidirectional"))
      (node (ref "JM1") (pin "12") (pinfunction "12_12") (pintype "bidirectional"))
      (node (ref "JM1") (pin "17") (pinfunction "17_17") (pintype "bidirectional"))
      (node (ref "JM1") (pin "18") (pinfunction "18_18") (pintype "bidirectional"))
      (node (ref "JM1") (pin "23") (pinfunction "23_23") (pintype "bidirectional"))
      (node (ref "JM1") (pin "24") (pinfunction "24_24") (pintype "bidirectional"))
      (node (ref "JM1") (pin "29") (pinfunction "29_29") (pintype "bidirectional"))
      (node (ref "JM1") (pin "30") (pinfunction "30_30") (pintype "bidirectional"))
      (node (ref "JM1") (pin "47") (pinfunction "47_47") (pintype "bidirectional"))
      (node (ref "JM1") (pin "48") (pinfunction "48_48") (pintype "bidirectional"))
      (node (ref "JM1") (pin "5") (pinfunction "5_5") (pintype "bidirectional"))
      (node (ref "JM1") (pin "6") (pinfunction "6_6") (pintype "bidirectional"))
      (node (ref "JM1") (pin "66") (pinfunction "66_66") (pintype "bidirectional"))
      (node (ref "JM1") (pin "84") (pinfunction "84_84") (pintype "bidirectional"))
      (node (ref "JM1") (pin "98") (pinfunction "98_98") (pintype "bidirectional"))
      (node (ref "JM1") (pin "F1") (pinfunction "F1_F1") (pintype "bidirectional"))
      (node (ref "JM1") (pin "F2") (pinfunction "F2_F2") (pintype "bidirectional"))
      (node (ref "JM2") (pin "17") (pinfunction "17_17") (pintype "bidirectional"))
      (node (ref "JM2") (pin "35") (pinfunction "35_35") (pintype "bidirectional"))
      (node (ref "JM2") (pin "36") (pinfunction "36_36") (pintype "bidirectional"))
      (node (ref "JM2") (pin "72") (pinfunction "72_72") (pintype "bidirectional"))
      (node (ref "JM2") (pin "83") (pinfunction "83_83") (pintype "bidirectional"))
      (node (ref "JM2") (pin "90") (pinfunction "90_90") (pintype "bidirectional"))
      (node (ref "JM2") (pin "F1") (pinfunction "F1_F1") (pintype "bidirectional"))
      (node (ref "JM2") (pin "F2") (pinfunction "F2_F2") (pintype "bidirectional"))
      (node (ref "JP1") (pin "3") (pinfunction "3_3") (pintype "passive"))
      (node (ref "JTAG") (pin "1") (pinfunction "1_1") (pintype "passive"))
      (node (ref "JTAG") (pin "11") (pinfunction "11_11") (pintype "passive"))
      (node (ref "JTAG") (pin "13") (pinfunction "13_13") (pintype "passive"))
      (node (ref "JTAG") (pin "3") (pinfunction "3_3") (pintype "passive"))
      (node (ref "JTAG") (pin "5") (pinfunction "5_5") (pintype "passive"))
      (node (ref "JTAG") (pin "7") (pinfunction "7_7") (pintype "passive"))
      (node (ref "JTAG") (pin "9") (pinfunction "9_9") (pintype "passive"))
      (node (ref "PCIE-NORTH") (pin "A1") (pinfunction "GND_A1") (pintype "passive"))
      (node (ref "PCIE-NORTH") (pin "A10") (pinfunction "GND_A10") (pintype "passive"))
      (node (ref "PCIE-NORTH") (pin "A12") (pinfunction "GND_A12") (pintype "passive"))
      (node (ref "PCIE-NORTH") (pin "A15") (pinfunction "GND_A15") (pintype "passive"))
      (node (ref "PCIE-NORTH") (pin "A18") (pinfunction "GND_A18") (pintype "passive"))
      (node (ref "PCIE-NORTH") (pin "A4") (pinfunction "GND_A4") (pintype "passive"))
      (node (ref "PCIE-NORTH") (pin "A7") (pinfunction "GND_A7") (pintype "passive"))
      (node (ref "PCIE-NORTH") (pin "B15") (pinfunction "GND_B15") (pintype "passive"))
      (node (ref "PCIE-NORTH") (pin "B18") (pinfunction "GND_B18") (pintype "passive"))
      (node (ref "PCIE-SOUTH") (pin "A1") (pinfunction "GND_A1") (pintype "passive"))
      (node (ref "PCIE-SOUTH") (pin "A10") (pinfunction "GND_A10") (pintype "passive"))
      (node (ref "PCIE-SOUTH") (pin "A12") (pinfunction "GND_A12") (pintype "passive"))
      (node (ref "PCIE-SOUTH") (pin "A15") (pinfunction "GND_A15") (pintype "passive"))
      (node (ref "PCIE-SOUTH") (pin "A18") (pinfunction "GND_A18") (pintype "passive"))
      (node (ref "PCIE-SOUTH") (pin "A4") (pinfunction "GND_A4") (pintype "passive"))
      (node (ref "PCIE-SOUTH") (pin "A7") (pinfunction "GND_A7") (pintype "passive"))
      (node (ref "PCIE-SOUTH") (pin "B15") (pinfunction "GND_B15") (pintype "passive"))
      (node (ref "PCIE-SOUTH") (pin "B18") (pinfunction "GND_B18") (pintype "passive"))
      (node (ref "R11") (pin "1") (pinfunction "1_1") (pintype "passive"))
      (node (ref "R3") (pin "2") (pinfunction "2_2") (pintype "passive"))
      (node (ref "SATA0") (pin "1") (pinfunction "GND_1") (pintype "power_in"))
      (node (ref "SATA0") (pin "4") (pinfunction "GND_4") (pintype "power_in"))
      (node (ref "SATA0") (pin "7") (pinfunction "GND_7") (pintype "power_in"))
      (node (ref "SATA1") (pin "1") (pinfunction "GND_1") (pintype "power_in"))
      (node (ref "SATA1") (pin "4") (pinfunction "GND_4") (pintype "power_in"))
      (node (ref "SATA1") (pin "7") (pinfunction "GND_7") (pintype "power_in"))
      (node (ref "SATA2") (pin "1") (pinfunction "GND_1") (pintype "power_in"))
      (node (ref "SATA2") (pin "4") (pinfunction "GND_4") (pintype "power_in"))
      (node (ref "SATA2") (pin "7") (pinfunction "GND_7") (pintype "power_in"))
      (node (ref "SATA3") (pin "1") (pinfunction "GND_1") (pintype "power_in"))
      (node (ref "SATA3") (pin "4") (pinfunction "GND_4") (pintype "power_in"))
      (node (ref "SATA3") (pin "7") (pinfunction "GND_7") (pintype "power_in"))
      (node (ref "U1") (pin "3") (pinfunction "GND_3") (pintype "passive"))
      (node (ref "U2") (pin "1") (pinfunction "A0_1") (pintype "input"))
      (node (ref "U2") (pin "2") (pinfunction "A1_2") (pintype "input"))
      (node (ref "U2") (pin "3") (pinfunction "A2_3") (pintype "input"))
      (node (ref "U2") (pin "4") (pinfunction "GND_4") (pintype "passive"))
      (node (ref "U2") (pin "EP") (pinfunction "EP_EP") (pintype "passive"))
      (node (ref "U7") (pin "5") (pinfunction "GND_5") (pintype "passive"))
      (node (ref "U7") (pin "6") (pinfunction "GND_6") (pintype "passive"))
      (node (ref "U7") (pin "EP") (pinfunction "GND_EP") (pintype "passive"))
    )
    (net (code "146") (name "I2C_V") (class "Default")
      (node (ref "C4") (pin "1") (pinfunction "1_1") (pintype "passive"))
      (node (ref "PCIE-NORTH") (pin "B3") (pinfunction "V_I2C_B3") (pintype "passive"))
      (node (ref "R2") (pin "1") (pinfunction "1_1") (pintype "passive"))
      (node (ref "U2") (pin "8") (pinfunction "VCC_8") (pintype "power_in"))
    )
    (net (code "147") (name "MGT_CLK0_N") (class "Default")
      (node (ref "C3") (pin "2") (pinfunction "2_2") (pintype "passive"))
      (node (ref "JM1") (pin "4") (pinfunction "4_4") (pintype "bidirectional"))
    )
    (net (code "148") (name "MGT_CLK0_P") (class "Default")
      (node (ref "C2") (pin "2") (pinfunction "2_2") (pintype "passive"))
      (node (ref "JM1") (pin "2") (pinfunction "2_2") (pintype "bidirectional"))
    )
    (net (code "149") (name "MGT_RX0_N") (class "Default")
      (node (ref "JM1") (pin "21") (pinfunction "21_21") (pintype "bidirectional"))
      (node (ref "SATA3") (pin "5") (pinfunction "~{B}_5") (pintype "bidirectional"))
    )
    (net (code "150") (name "MGT_RX0_P") (class "Default")
      (node (ref "JM1") (pin "19") (pinfunction "19_19") (pintype "bidirectional"))
      (node (ref "SATA3") (pin "6") (pinfunction "B_6") (pintype "bidirectional"))
    )
    (net (code "151") (name "MGT_RX1_N") (class "Default")
      (node (ref "JM1") (pin "15") (pinfunction "15_15") (pintype "bidirectional"))
      (node (ref "SATA2") (pin "5") (pinfunction "~{B}_5") (pintype "bidirectional"))
    )
    (net (code "152") (name "MGT_RX1_P") (class "Default")
      (node (ref "JM1") (pin "13") (pinfunction "13_13") (pintype "bidirectional"))
      (node (ref "SATA2") (pin "6") (pinfunction "B_6") (pintype "bidirectional"))
    )
    (net (code "153") (name "MGT_RX2_N") (class "Default")
      (node (ref "JM1") (pin "9") (pinfunction "9_9") (pintype "bidirectional"))
      (node (ref "SATA1") (pin "5") (pinfunction "~{B}_5") (pintype "bidirectional"))
    )
    (net (code "154") (name "MGT_RX2_P") (class "Default")
      (node (ref "JM1") (pin "7") (pinfunction "7_7") (pintype "bidirectional"))
      (node (ref "SATA1") (pin "6") (pinfunction "B_6") (pintype "bidirectional"))
    )
    (net (code "155") (name "MGT_RX3_N") (class "Default")
      (node (ref "JM1") (pin "3") (pinfunction "3_3") (pintype "bidirectional"))
      (node (ref "SATA0") (pin "5") (pinfunction "~{B}_5") (pintype "bidirectional"))
    )
    (net (code "156") (name "MGT_RX3_P") (class "Default")
      (node (ref "JM1") (pin "1") (pinfunction "1_1") (pintype "bidirectional"))
      (node (ref "SATA0") (pin "6") (pinfunction "B_6") (pintype "bidirectional"))
    )
    (net (code "157") (name "MGT_TX0_N") (class "Default")
      (node (ref "JM1") (pin "28") (pinfunction "28_28") (pintype "bidirectional"))
      (node (ref "SATA3") (pin "3") (pinfunction "~{A}_3") (pintype "bidirectional"))
    )
    (net (code "158") (name "MGT_TX0_P") (class "Default")
      (node (ref "JM1") (pin "26") (pinfunction "26_26") (pintype "bidirectional"))
      (node (ref "SATA3") (pin "2") (pinfunction "A_2") (pintype "bidirectional"))
    )
    (net (code "159") (name "MGT_TX1_N") (class "Default")
      (node (ref "JM1") (pin "22") (pinfunction "22_22") (pintype "bidirectional"))
      (node (ref "SATA2") (pin "3") (pinfunction "~{A}_3") (pintype "bidirectional"))
    )
    (net (code "160") (name "MGT_TX1_P") (class "Default")
      (node (ref "JM1") (pin "20") (pinfunction "20_20") (pintype "bidirectional"))
      (node (ref "SATA2") (pin "2") (pinfunction "A_2") (pintype "bidirectional"))
    )
    (net (code "161") (name "MGT_TX2_N") (class "Default")
      (node (ref "JM1") (pin "16") (pinfunction "16_16") (pintype "bidirectional"))
      (node (ref "SATA1") (pin "3") (pinfunction "~{A}_3") (pintype "bidirectional"))
    )
    (net (code "162") (name "MGT_TX2_P") (class "Default")
      (node (ref "JM1") (pin "14") (pinfunction "14_14") (pintype "bidirectional"))
      (node (ref "SATA1") (pin "2") (pinfunction "A_2") (pintype "bidirectional"))
    )
    (net (code "163") (name "MGT_TX3_N") (class "Default")
      (node (ref "JM1") (pin "10") (pinfunction "10_10") (pintype "bidirectional"))
      (node (ref "SATA0") (pin "3") (pinfunction "~{A}_3") (pintype "bidirectional"))
    )
    (net (code "164") (name "MGT_TX3_P") (class "Default")
      (node (ref "JM1") (pin "8") (pinfunction "8_8") (pintype "bidirectional"))
      (node (ref "SATA0") (pin "2") (pinfunction "A_2") (pintype "bidirectional"))
    )
    (net (code "165") (name "M_1V8") (class "Default")
      (node (ref "JM2") (pin "18") (pinfunction "18_18") (pintype "bidirectional"))
    )
    (net (code "166") (name "N_5V") (class "Default")
      (node (ref "PCIE-NORTH") (pin "B12") (pinfunction "5V_B12") (pintype "passive"))
    )
    (net (code "167") (name "N_IO0") (class "Default")
      (node (ref "PCIE-NORTH") (pin "B4") (pinfunction "IO0_B4") (pintype "passive"))
    )
    (net (code "168") (name "N_IO1") (class "Default")
      (node (ref "PCIE-NORTH") (pin "B5") (pinfunction "IO1_B5") (pintype "passive"))
    )
    (net (code "169") (name "N_IO2") (class "Default")
      (node (ref "PCIE-NORTH") (pin "B6") (pinfunction "IO2_B6") (pintype "passive"))
    )
    (net (code "170") (name "N_IO3") (class "Default")
      (node (ref "PCIE-NORTH") (pin "B7") (pinfunction "IO3_B7") (pintype "passive"))
    )
    (net (code "171") (name "N_IO4") (class "Default")
      (node (ref "PCIE-NORTH") (pin "B8") (pinfunction "IO4_B8") (pintype "passive"))
    )
    (net (code "172") (name "N_IO5") (class "Default")
      (node (ref "PCIE-NORTH") (pin "B9") (pinfunction "IO5_B9") (pintype "passive"))
    )
    (net (code "173") (name "N_IO6") (class "Default")
      (node (ref "PCIE-NORTH") (pin "B10") (pinfunction "IO6_B10") (pintype "passive"))
    )
    (net (code "174") (name "N_IO7") (class "Default")
      (node (ref "PCIE-NORTH") (pin "B11") (pinfunction "IO7_B11") (pintype "passive"))
    )
    (net (code "175") (name "N_PCIE_V") (class "Default")
      (node (ref "PCIE-NORTH") (pin "B13") (pinfunction "VCC_B13") (pintype "passive"))
    )
    (net (code "176") (name "N_VCCIO") (class "Default")
      (node (ref "PCIE-NORTH") (pin "B14") (pinfunction "VCCIO_B14") (pintype "passive"))
    )
    (net (code "177") (name "Net-(D1-PadC)") (class "Default")
      (node (ref "D1") (pin "C") (pinfunction "C_C") (pintype "passive"))
      (node (ref "R5") (pin "2") (pinfunction "2_2") (pintype "passive"))
    )
    (net (code "178") (name "Net-(D2-PadC)") (class "Default")
      (node (ref "D2") (pin "C") (pinfunction "C_C") (pintype "passive"))
      (node (ref "R6") (pin "2") (pinfunction "2_2") (pintype "passive"))
    )
    (net (code "179") (name "Net-(D3-PadC)") (class "Default")
      (node (ref "D3") (pin "C") (pinfunction "C_C") (pintype "passive"))
      (node (ref "R7") (pin "2") (pinfunction "2_2") (pintype "passive"))
    )
    (net (code "180") (name "Net-(D4-PadC)") (class "Default")
      (node (ref "D4") (pin "C") (pinfunction "C_C") (pintype "passive"))
      (node (ref "R8") (pin "2") (pinfunction "2_2") (pintype "passive"))
    )
    (net (code "181") (name "Net-(U1-OUT+)") (class "Default")
      (node (ref "C2") (pin "1") (pinfunction "1_1") (pintype "passive"))
      (node (ref "R1") (pin "1") (pinfunction "1_1") (pintype "passive"))
      (node (ref "U1") (pin "4") (pinfunction "OUT+_4") (pintype "output"))
    )
    (net (code "182") (name "Net-(U1-OUT-)") (class "Default")
      (node (ref "C3") (pin "1") (pinfunction "1_1") (pintype "passive"))
      (node (ref "R1") (pin "2") (pinfunction "2_2") (pintype "passive"))
      (node (ref "U1") (pin "5") (pinfunction "OUT-_5") (pintype "output"))
    )
    (net (code "183") (name "Net-(U2-WP)") (class "Default")
      (node (ref "R2") (pin "2") (pinfunction "2_2") (pintype "passive"))
      (node (ref "R3") (pin "1") (pinfunction "1_1") (pintype "passive"))
      (node (ref "U2") (pin "7") (pinfunction "WP_7") (pintype "input"))
    )
    (net (code "184") (name "Net-(U7-FB)") (class "Default")
      (node (ref "R10") (pin "1") (pinfunction "1_1") (pintype "passive"))
      (node (ref "R11") (pin "2") (pinfunction "2_2") (pintype "passive"))
      (node (ref "U7") (pin "7") (pinfunction "FB_7") (pintype "output"))
    )
    (net (code "185") (name "PROG_B") (class "Default")
      (node (ref "JM1") (pin "94") (pinfunction "94_94") (pintype "bidirectional"))
    )
    (net (code "186") (name "SCL") (class "Default")
      (node (ref "PCIE-NORTH") (pin "B2") (pinfunction "SCL_B2") (pintype "passive"))
      (node (ref "U2") (pin "6") (pinfunction "SCL_6") (pintype "input"))
    )
    (net (code "187") (name "SDA") (class "Default")
      (node (ref "PCIE-NORTH") (pin "B1") (pinfunction "SDA_B1") (pintype "passive"))
      (node (ref "U2") (pin "5") (pinfunction "SDA_5") (pintype "bidirectional"))
    )
    (net (code "188") (name "SPI-CLK") (class "Default")
      (node (ref "JM2") (pin "67") (pinfunction "67_67") (pintype "bidirectional"))
    )
    (net (code "189") (name "SPI-CS") (class "Default")
      (node (ref "JM2") (pin "69") (pinfunction "69_69") (pintype "bidirectional"))
    )
    (net (code "190") (name "SPI-DQ0") (class "Default")
      (node (ref "JM2") (pin "68") (pinfunction "68_68") (pintype "bidirectional"))
    )
    (net (code "191") (name "SPI-DQ1") (class "Default")
      (node (ref "JM2") (pin "71") (pinfunction "71_71") (pintype "bidirectional"))
    )
    (net (code "192") (name "SPI-DQ2") (class "Default")
      (node (ref "JM2") (pin "73") (pinfunction "73_73") (pintype "bidirectional"))
    )
    (net (code "193") (name "SPI-DQ3") (class "Default")
      (node (ref "JM2") (pin "70") (pinfunction "70_70") (pintype "bidirectional"))
    )
    (net (code "194") (name "S_5V") (class "Default")
      (node (ref "JP1") (pin "1") (pinfunction "1_1") (pintype "passive"))
      (node (ref "PCIE-SOUTH") (pin "B12") (pinfunction "5V_B12") (pintype "passive"))
    )
    (net (code "195") (name "S_PCIE_V") (class "Default")
      (node (ref "PCIE-SOUTH") (pin "B13") (pinfunction "VCC_B13") (pintype "passive"))
    )
    (net (code "196") (name "S_VCCIO") (class "Default")
      (node (ref "JM2") (pin "54") (pinfunction "54_54") (pintype "bidirectional"))
      (node (ref "PCIE-SOUTH") (pin "B14") (pinfunction "VCCIO_B14") (pintype "passive"))
    )
    (net (code "197") (name "TCK") (class "Default")
      (node (ref "JM1") (pin "90") (pinfunction "90_90") (pintype "bidirectional"))
      (node (ref "JTAG") (pin "6") (pinfunction "6_6") (pintype "passive"))
    )
    (net (code "198") (name "TDI") (class "Default")
      (node (ref "JM1") (pin "86") (pinfunction "86_86") (pintype "bidirectional"))
      (node (ref "JTAG") (pin "10") (pinfunction "10_10") (pintype "passive"))
    )
    (net (code "199") (name "TDO") (class "Default")
      (node (ref "JM1") (pin "88") (pinfunction "88_88") (pintype "bidirectional"))
      (node (ref "JTAG") (pin "8") (pinfunction "8_8") (pintype "passive"))
    )
    (net (code "200") (name "TMS") (class "Default")
      (node (ref "JM1") (pin "92") (pinfunction "92_92") (pintype "bidirectional"))
      (node (ref "JTAG") (pin "4") (pinfunction "4_4") (pintype "passive"))
    )
    (net (code "201") (name "VCCIO0") (class "Default")
      (node (ref "JM2") (pin "53") (pinfunction "53_53") (pintype "bidirectional"))
      (node (ref "JTAG") (pin "2") (pinfunction "2_2") (pintype "passive"))
    )
    (net (code "202") (name "VOUT_B") (class "Default")
      (node (ref "C6") (pin "1") (pinfunction "1_1") (pintype "passive"))
      (node (ref "FB2") (pin "1") (pinfunction "1_1") (pintype "passive"))
      (node (ref "R10") (pin "2") (pinfunction "2_2") (pintype "passive"))
      (node (ref "U7") (pin "8") (pinfunction "VOUT_8") (pintype "output"))
    )
    (net (code "203") (name "VSUP") (class "Default")
      (node (ref "C5") (pin "1") (pinfunction "1_1") (pintype "passive"))
      (node (ref "JP1") (pin "2") (pinfunction "2_2") (pintype "passive"))
      (node (ref "R9") (pin "2") (pinfunction "2_2") (pintype "passive"))
      (node (ref "U7") (pin "3") (pinfunction "VIN_3") (pintype "power_in"))
      (node (ref "U7") (pin "4") (pinfunction "VIN_4") (pintype "power_in"))
    )
    (net (code "204") (name "V_CLK") (class "Default")
      (node (ref "C1") (pin "1") (pinfunction "1_1") (pintype "passive"))
      (node (ref "FB1") (pin "2") (pinfunction "2_2") (pintype "passive"))
      (node (ref "U1") (pin "6") (pinfunction "VCC_6") (pintype "power_in"))
    )
    (net (code "205") (name "unconnected-(JTAG-Pad12)") (class "Default")
      (node (ref "JTAG") (pin "12") (pinfunction "12_12") (pintype "passive"))
    )
    (net (code "206") (name "unconnected-(JTAG-Pad14)") (class "Default")
      (node (ref "JTAG") (pin "14") (pinfunction "14_14") (pintype "passive"))
    )
    (net (code "207") (name "unconnected-(PCIE-NORTH-PWRGD-PadA11)") (class "Default")
      (node (ref "PCIE-NORTH") (pin "A11") (pinfunction "PWRGD_A11") (pintype "passive"))
    )
    (net (code "208") (name "unconnected-(PCIE-SOUTH-PWRGD-PadA11)") (class "Default")
      (node (ref "PCIE-SOUTH") (pin "A11") (pinfunction "PWRGD_A11") (pintype "passive"))
    )
    (net (code "209") (name "unconnected-(PCIE-SOUTH-SCL-PadB2)") (class "Default")
      (node (ref "PCIE-SOUTH") (pin "B2") (pinfunction "SCL_B2") (pintype "passive"))
    )
    (net (code "210") (name "unconnected-(PCIE-SOUTH-SDA-PadB1)") (class "Default")
      (node (ref "PCIE-SOUTH") (pin "B1") (pinfunction "SDA_B1") (pintype "passive"))
    )
    (net (code "211") (name "unconnected-(PCIE-SOUTH-V_I2C-PadB3)") (class "Default")
      (node (ref "PCIE-SOUTH") (pin "B3") (pinfunction "V_I2C_B3") (pintype "passive"))
    )
  )
)
